# TTP224.net
KiCad netlist of a schematic drawn in Altium Designer
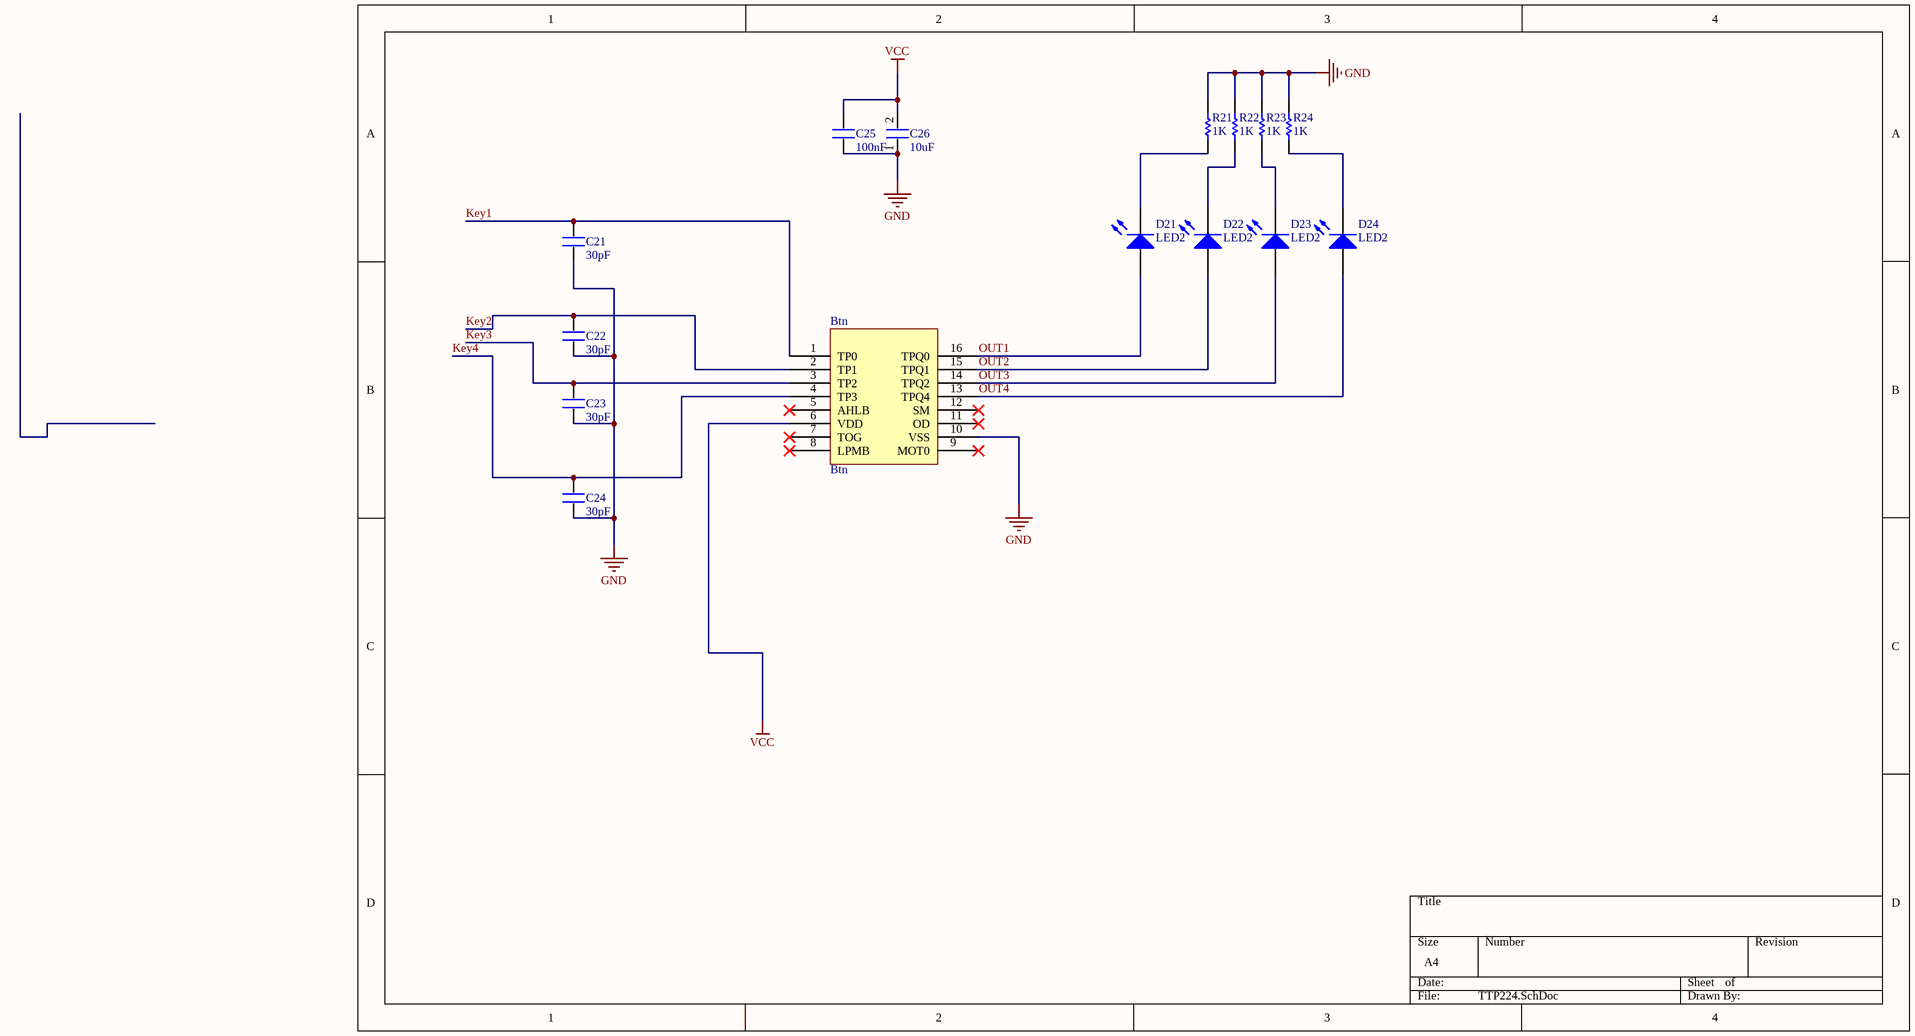
[diagram p0: TTP224.SchDoc]

(export (version "E")
  (design (tool "Eeschema 10.0.6"))
  (components
    (comp (ref "Btn") (value "Btn") (footprint "SOP64P600X175-16N") (libsource (lib "lib") (part "Btn")))
    (comp (ref "C21")
      (value "30pF")
      (footprint "0805")
      (description "Capacitor")
      (fields (field (name "Comment") "CAP"))
      (libsource (lib "lib") (part "CAP"))
    )
    (comp (ref "C22")
      (value "30pF")
      (footprint "0805")
      (description "Capacitor")
      (fields (field (name "Comment") "CAP"))
      (libsource (lib "lib") (part "CAP"))
    )
    (comp (ref "C23")
      (value "30pF")
      (footprint "0805")
      (description "Capacitor")
      (fields (field (name "Comment") "CAP"))
      (libsource (lib "lib") (part "CAP"))
    )
    (comp (ref "C24")
      (value "30pF")
      (footprint "0805")
      (description "Capacitor")
      (fields (field (name "Comment") "CAP"))
      (libsource (lib "lib") (part "CAP"))
    )
    (comp (ref "C25")
      (value "100nF")
      (footprint "0805")
      (description "Capacitor")
      (fields (field (name "Comment") "CAP"))
      (libsource (lib "lib") (part "CAP"))
    )
    (comp (ref "C26")
      (value "10uF")
      (footprint "0805")
      (description "Capacitor")
      (fields (field (name "Comment") "CAP"))
      (libsource (lib "") (part "CAP_1"))
    )
    (comp (ref "D21")
      (value "LED2")
      (footprint "3.2X1.6X1.1")
      (description "Typical RED, GREEN, YELLOW, AMBER GaAs LED")
      (fields (field (name "PUBLISHER") "Altium Limited"))
      (libsource (lib "lib") (part "LED2"))
    )
    (comp (ref "D22")
      (value "LED2")
      (footprint "3.2X1.6X1.1")
      (description "Typical RED, GREEN, YELLOW, AMBER GaAs LED")
      (fields (field (name "PUBLISHER") "Altium Limited"))
      (libsource (lib "lib") (part "LED2"))
    )
    (comp (ref "D23")
      (value "LED2")
      (footprint "3.2X1.6X1.1")
      (description "Typical RED, GREEN, YELLOW, AMBER GaAs LED")
      (fields (field (name "PUBLISHER") "Altium Limited"))
      (libsource (lib "lib") (part "LED2"))
    )
    (comp (ref "D24")
      (value "LED2")
      (footprint "3.2X1.6X1.1")
      (description "Typical RED, GREEN, YELLOW, AMBER GaAs LED")
      (fields (field (name "PUBLISHER") "Altium Limited"))
      (libsource (lib "lib") (part "LED2"))
    )
    (comp (ref "R21")
      (value "RES")
      (footprint "0805")
      (description "Resistor")
      (fields (field (name "VAULE") "1K"))
      (libsource (lib "lib") (part "RES"))
    )
    (comp (ref "R22")
      (value "RES")
      (footprint "0805")
      (description "Resistor")
      (fields (field (name "VAULE") "1K"))
      (libsource (lib "lib") (part "RES"))
    )
    (comp (ref "R23")
      (value "RES")
      (footprint "0805")
      (description "Resistor")
      (fields (field (name "VAULE") "1K"))
      (libsource (lib "lib") (part "RES"))
    )
    (comp (ref "R24")
      (value "RES")
      (footprint "0805")
      (description "Resistor")
      (fields (field (name "VAULE") "1K"))
      (libsource (lib "lib") (part "RES"))
    )
  )
  (nets
    (net (code "1") (name "/Key1") (class "Default")
      (node (ref "Btn") (pin "1") (pinfunction "TP0_1") (pintype "passive"))
      (node (ref "C21") (pin "2") (pintype "passive"))
    )
    (net (code "2") (name "/Key2") (class "Default")
      (node (ref "Btn") (pin "2") (pinfunction "TP1_2") (pintype "passive"))
      (node (ref "C22") (pin "2") (pintype "passive"))
    )
    (net (code "3") (name "/Key3") (class "Default")
      (node (ref "Btn") (pin "3") (pinfunction "TP2_3") (pintype "passive"))
      (node (ref "C23") (pin "2") (pintype "passive"))
    )
    (net (code "4") (name "/Key4") (class "Default")
      (node (ref "Btn") (pin "4") (pinfunction "TP3_4") (pintype "passive"))
      (node (ref "C24") (pin "2") (pintype "passive"))
    )
    (net (code "5") (name "/OUT1") (class "Default")
      (node (ref "Btn") (pin "16") (pinfunction "TPQ0_16") (pintype "passive"))
      (node (ref "D21") (pin "1") (pinfunction "A_1") (pintype "passive"))
    )
    (net (code "6") (name "/OUT2") (class "Default")
      (node (ref "Btn") (pin "15") (pinfunction "TPQ1_15") (pintype "passive"))
      (node (ref "D22") (pin "1") (pinfunction "A_1") (pintype "passive"))
    )
    (net (code "7") (name "/OUT3") (class "Default")
      (node (ref "Btn") (pin "14") (pinfunction "TPQ2_14") (pintype "passive"))
      (node (ref "D23") (pin "1") (pinfunction "A_1") (pintype "passive"))
    )
    (net (code "8") (name "/OUT4") (class "Default")
      (node (ref "Btn") (pin "13") (pinfunction "TPQ4_13") (pintype "passive"))
      (node (ref "D24") (pin "1") (pinfunction "A_1") (pintype "passive"))
    )
    (net (code "9") (name "GND") (class "Default")
      (node (ref "Btn") (pin "10") (pinfunction "VSS_10") (pintype "passive"))
      (node (ref "C21") (pin "1") (pintype "passive"))
      (node (ref "C22") (pin "1") (pintype "passive"))
      (node (ref "C23") (pin "1") (pintype "passive"))
      (node (ref "C24") (pin "1") (pintype "passive"))
      (node (ref "C25") (pin "1") (pintype "passive"))
      (node (ref "C26") (pin "1") (pinfunction "1_1") (pintype "passive"))
      (node (ref "R21") (pin "2") (pinfunction "2_2") (pintype "passive"))
      (node (ref "R22") (pin "2") (pinfunction "2_2") (pintype "passive"))
      (node (ref "R23") (pin "2") (pinfunction "2_2") (pintype "passive"))
      (node (ref "R24") (pin "2") (pinfunction "2_2") (pintype "passive"))
    )
    (net (code "10") (name "Net-(D21-K)") (class "Default")
      (node (ref "D21") (pin "2") (pinfunction "K_2") (pintype "passive"))
      (node (ref "R21") (pin "1") (pinfunction "1_1") (pintype "passive"))
    )
    (net (code "11") (name "Net-(D22-K)") (class "Default")
      (node (ref "D22") (pin "2") (pinfunction "K_2") (pintype "passive"))
      (node (ref "R22") (pin "1") (pinfunction "1_1") (pintype "passive"))
    )
    (net (code "12") (name "Net-(D23-K)") (class "Default")
      (node (ref "D23") (pin "2") (pinfunction "K_2") (pintype "passive"))
      (node (ref "R23") (pin "1") (pinfunction "1_1") (pintype "passive"))
    )
    (net (code "13") (name "Net-(D24-K)") (class "Default")
      (node (ref "D24") (pin "2") (pinfunction "K_2") (pintype "passive"))
      (node (ref "R24") (pin "1") (pinfunction "1_1") (pintype "passive"))
    )
    (net (code "14") (name "VCC") (class "Default")
      (node (ref "Btn") (pin "6") (pinfunction "VDD_6") (pintype "passive"))
      (node (ref "C25") (pin "2") (pintype "passive"))
      (node (ref "C26") (pin "2") (pinfunction "2_2") (pintype "passive"))
    )
    (net (code "15") (name "unconnected-(Btn-AHLB-Pad5)") (class "Default")
      (node (ref "Btn") (pin "5") (pinfunction "AHLB_5") (pintype "passive+no_connect"))
    )
    (net (code "16") (name "unconnected-(Btn-LPMB-Pad8)") (class "Default")
      (node (ref "Btn") (pin "8") (pinfunction "LPMB_8") (pintype "passive+no_connect"))
    )
    (net (code "17") (name "unconnected-(Btn-MOT0-Pad9)") (class "Default")
      (node (ref "Btn") (pin "9") (pinfunction "MOT0_9") (pintype "passive+no_connect"))
    )
    (net (code "18") (name "unconnected-(Btn-OD-Pad11)") (class "Default")
      (node (ref "Btn") (pin "11") (pinfunction "OD_11") (pintype "passive+no_connect"))
    )
    (net (code "19") (name "unconnected-(Btn-SM-Pad12)") (class "Default")
      (node (ref "Btn") (pin "12") (pinfunction "SM_12") (pintype "passive+no_connect"))
    )
    (net (code "20") (name "unconnected-(Btn-TOG-Pad7)") (class "Default")
      (node (ref "Btn") (pin "7") (pinfunction "TOG_7") (pintype "passive+no_connect"))
    )
  )
)
